# BMI088.net
KiCad netlist of a schematic drawn in Altium Designer
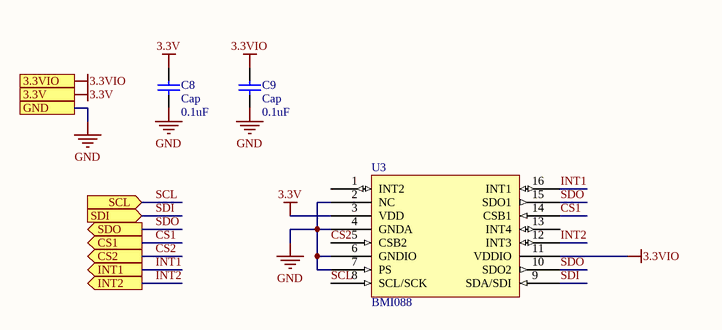
[diagram p0: BMI088.SchDoc]

(export (version "E")
  (design (tool "Eeschema 10.0.6"))
  (components
    (comp (ref "C8")
      (value "Cap")
      (footprint "0603")
      (description "Capacitor")
      (fields (field (name "ALTIUM_VALUE") "0.1uF") (field (name "PUBLISHER") "Altium Limited"))
      (libsource (lib "Miscellaneous Devices") (part "Cap"))
    )
    (comp (ref "C9")
      (value "Cap")
      (footprint "0603")
      (description "Capacitor")
      (fields (field (name "ALTIUM_VALUE") "0.1uF") (field (name "PUBLISHER") "Altium Limited"))
      (libsource (lib "Miscellaneous Devices") (part "Cap"))
    )
    (comp (ref "U3") (value "BMI088") (footprint "BMI088") (libsource (lib "SchlibSensors") (part "BMI088")))
  )
  (nets
    (net (code "1") (name "/CS1") (class "Default")
      (node (ref "U3") (pin "14") (pinfunction "CSB1_14") (pintype "input"))
    )
    (net (code "2") (name "/CS2") (class "Default")
      (node (ref "U3") (pin "5") (pinfunction "CSB2_5") (pintype "input"))
    )
    (net (code "3") (name "/INT1") (class "Default")
      (node (ref "U3") (pin "16") (pinfunction "INT1_16") (pintype "bidirectional"))
    )
    (net (code "4") (name "/INT2") (class "Default")
      (node (ref "U3") (pin "12") (pinfunction "INT3_12") (pintype "bidirectional"))
    )
    (net (code "5") (name "/SCL") (class "Default")
      (node (ref "U3") (pin "8") (pinfunction "SCL/SCK_8") (pintype "input"))
    )
    (net (code "6") (name "/SDI") (class "Default")
      (node (ref "U3") (pin "9") (pinfunction "SDA/SDI_9") (pintype "input"))
    )
    (net (code "7") (name "/SDO") (class "Default")
      (node (ref "U3") (pin "10") (pinfunction "SDO2_10") (pintype "output"))
      (node (ref "U3") (pin "15") (pinfunction "SDO1_15") (pintype "output"))
    )
    (net (code "8") (name "3.3V") (class "Default")
      (node (ref "C8") (pin "1") (pinfunction "1_1") (pintype "passive"))
      (node (ref "U3") (pin "3") (pinfunction "VDD_3") (pintype "power_in"))
    )
    (net (code "9") (name "3.3VIO") (class "Default")
      (node (ref "C9") (pin "1") (pinfunction "1_1") (pintype "passive"))
      (node (ref "U3") (pin "11") (pinfunction "VDDIO_11") (pintype "power_in"))
    )
    (net (code "10") (name "GND") (class "Default")
      (node (ref "C8") (pin "2") (pinfunction "2_2") (pintype "passive"))
      (node (ref "C9") (pin "2") (pinfunction "2_2") (pintype "passive"))
      (node (ref "U3") (pin "2") (pinfunction "NC_2") (pintype "passive"))
      (node (ref "U3") (pin "4") (pinfunction "GNDA_4") (pintype "power_in"))
      (node (ref "U3") (pin "6") (pinfunction "GNDIO_6") (pintype "power_in"))
      (node (ref "U3") (pin "7") (pinfunction "PS_7") (pintype "input"))
    )
    (net (code "11") (name "unconnected-(U3-INT2-Pad1)") (class "Default")
      (node (ref "U3") (pin "1") (pinfunction "INT2_1") (pintype "bidirectional"))
    )
    (net (code "12") (name "unconnected-(U3-INT4-Pad13)") (class "Default")
      (node (ref "U3") (pin "13") (pinfunction "INT4_13") (pintype "bidirectional"))
    )
  )
)
